# quad.net
KiCad netlist of a schematic drawn in EAGLE
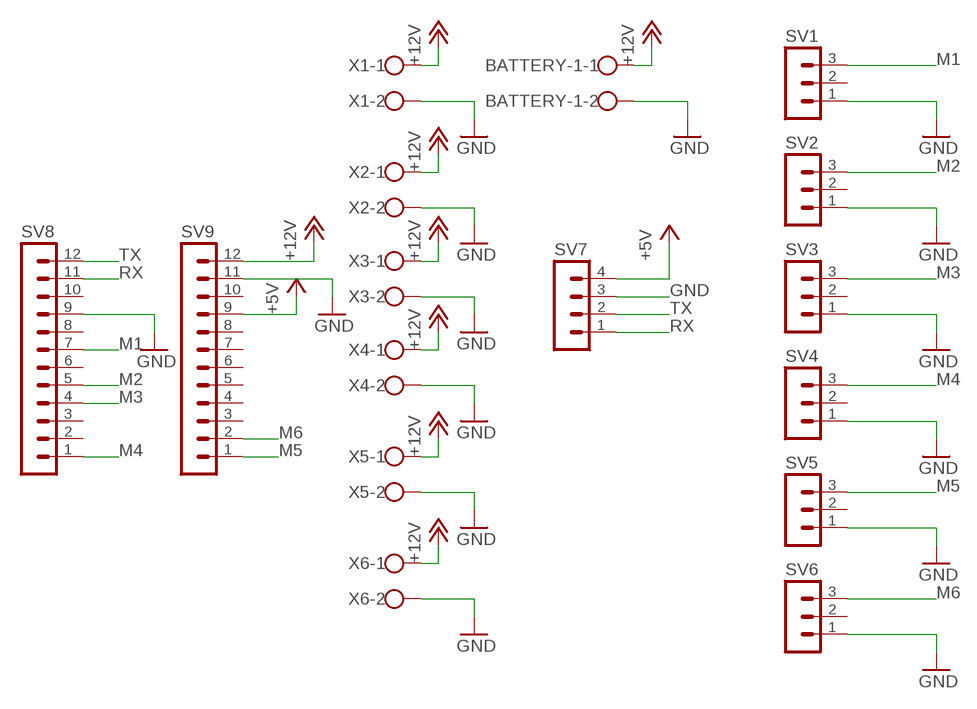
[diagram p0: schematic, sheet 1]

(export (version "E")
  (design (tool "Eeschema 10.0.6"))
  (components
    (comp (ref "BATTERY-1")
      (value "W237-102")
      (footprint "eagle-import:W237-102")
      (fields (field (name "MPN") "237-102"))
      (libsource (lib "eagle-import") (part "W237-102"))
    )
    (comp (ref "SV1")
      (value "MA03-1")
      (footprint "eagle-import:MA03-1")
      (libsource (lib "eagle-import") (part "MA03-1"))
    )
    (comp (ref "SV2")
      (value "MA03-1")
      (footprint "eagle-import:MA03-1")
      (libsource (lib "eagle-import") (part "MA03-1"))
    )
    (comp (ref "SV3")
      (value "MA03-1")
      (footprint "eagle-import:MA03-1")
      (libsource (lib "eagle-import") (part "MA03-1"))
    )
    (comp (ref "SV4")
      (value "MA03-1")
      (footprint "eagle-import:MA03-1")
      (libsource (lib "eagle-import") (part "MA03-1"))
    )
    (comp (ref "SV5")
      (value "MA03-1")
      (footprint "eagle-import:MA03-1")
      (libsource (lib "eagle-import") (part "MA03-1"))
    )
    (comp (ref "SV6")
      (value "MA03-1")
      (footprint "eagle-import:MA03-1")
      (libsource (lib "eagle-import") (part "MA03-1"))
    )
    (comp (ref "SV7")
      (value "MA04-1")
      (footprint "eagle-import:MA04-1")
      (libsource (lib "eagle-import") (part "MA04-1"))
    )
    (comp (ref "SV8")
      (value "MA12-1")
      (footprint "eagle-import:MA12-1")
      (libsource (lib "eagle-import") (part "MA12-1"))
    )
    (comp (ref "SV9")
      (value "MA12-1")
      (footprint "eagle-import:MA12-1")
      (libsource (lib "eagle-import") (part "MA12-1"))
    )
    (comp (ref "X1")
      (value "W237-102")
      (footprint "eagle-import:W237-102")
      (fields (field (name "MPN") "237-102"))
      (libsource (lib "eagle-import") (part "W237-102"))
    )
    (comp (ref "X2")
      (value "W237-102")
      (footprint "eagle-import:W237-102")
      (fields (field (name "MPN") "237-102"))
      (libsource (lib "eagle-import") (part "W237-102"))
    )
    (comp (ref "X3")
      (value "W237-102")
      (footprint "eagle-import:W237-102")
      (fields (field (name "MPN") "237-102"))
      (libsource (lib "eagle-import") (part "W237-102"))
    )
    (comp (ref "X4")
      (value "W237-102")
      (footprint "eagle-import:W237-102")
      (fields (field (name "MPN") "237-102"))
      (libsource (lib "eagle-import") (part "W237-102"))
    )
    (comp (ref "X5")
      (value "W237-102")
      (footprint "eagle-import:W237-102")
      (fields (field (name "MPN") "237-102"))
      (libsource (lib "eagle-import") (part "W237-102"))
    )
    (comp (ref "X6")
      (value "W237-102")
      (footprint "eagle-import:W237-102")
      (fields (field (name "MPN") "237-102"))
      (libsource (lib "eagle-import") (part "W237-102"))
    )
  )
  (nets
    (net (code "1") (name "+5V") (class "Default")
      (node (ref "SV7") (pin "4") (pinfunction "4_4") (pintype "passive"))
      (node (ref "SV9") (pin "9") (pinfunction "9_9") (pintype "passive"))
    )
    (net (code "2") (name "+12V") (class "Default")
      (node (ref "BATTERY-1") (pin "1") (pinfunction "KL_1") (pintype "passive"))
      (node (ref "SV9") (pin "12") (pinfunction "12_12") (pintype "passive"))
      (node (ref "X1") (pin "1") (pinfunction "KL_1") (pintype "passive"))
      (node (ref "X2") (pin "1") (pinfunction "KL_1") (pintype "passive"))
      (node (ref "X3") (pin "1") (pinfunction "KL_1") (pintype "passive"))
      (node (ref "X4") (pin "1") (pinfunction "KL_1") (pintype "passive"))
      (node (ref "X5") (pin "1") (pinfunction "KL_1") (pintype "passive"))
      (node (ref "X6") (pin "1") (pinfunction "KL_1") (pintype "passive"))
    )
    (net (code "3") (name "/M1") (class "Default")
      (node (ref "SV1") (pin "3") (pinfunction "3_3") (pintype "passive"))
      (node (ref "SV8") (pin "7") (pinfunction "7_7") (pintype "passive"))
    )
    (net (code "4") (name "/M2") (class "Default")
      (node (ref "SV2") (pin "3") (pinfunction "3_3") (pintype "passive"))
      (node (ref "SV8") (pin "5") (pinfunction "5_5") (pintype "passive"))
    )
    (net (code "5") (name "/M3") (class "Default")
      (node (ref "SV3") (pin "3") (pinfunction "3_3") (pintype "passive"))
      (node (ref "SV8") (pin "4") (pinfunction "4_4") (pintype "passive"))
    )
    (net (code "6") (name "/M4") (class "Default")
      (node (ref "SV4") (pin "3") (pinfunction "3_3") (pintype "passive"))
      (node (ref "SV8") (pin "1") (pinfunction "1_1") (pintype "passive"))
    )
    (net (code "7") (name "/M5") (class "Default")
      (node (ref "SV5") (pin "3") (pinfunction "3_3") (pintype "passive"))
      (node (ref "SV9") (pin "1") (pinfunction "1_1") (pintype "passive"))
    )
    (net (code "8") (name "/M6") (class "Default")
      (node (ref "SV6") (pin "3") (pinfunction "3_3") (pintype "passive"))
      (node (ref "SV9") (pin "2") (pinfunction "2_2") (pintype "passive"))
    )
    (net (code "9") (name "/RX") (class "Default")
      (node (ref "SV7") (pin "1") (pinfunction "1_1") (pintype "passive"))
      (node (ref "SV8") (pin "11") (pinfunction "11_11") (pintype "passive"))
    )
    (net (code "10") (name "/TX") (class "Default")
      (node (ref "SV7") (pin "2") (pinfunction "2_2") (pintype "passive"))
      (node (ref "SV8") (pin "12") (pinfunction "12_12") (pintype "passive"))
    )
    (net (code "11") (name "GND") (class "Default")
      (node (ref "BATTERY-1") (pin "2") (pinfunction "KL_2") (pintype "passive"))
      (node (ref "SV1") (pin "1") (pinfunction "1_1") (pintype "passive"))
      (node (ref "SV2") (pin "1") (pinfunction "1_1") (pintype "passive"))
      (node (ref "SV3") (pin "1") (pinfunction "1_1") (pintype "passive"))
      (node (ref "SV4") (pin "1") (pinfunction "1_1") (pintype "passive"))
      (node (ref "SV5") (pin "1") (pinfunction "1_1") (pintype "passive"))
      (node (ref "SV6") (pin "1") (pinfunction "1_1") (pintype "passive"))
      (node (ref "SV7") (pin "3") (pinfunction "3_3") (pintype "passive"))
      (node (ref "SV8") (pin "9") (pinfunction "9_9") (pintype "passive"))
      (node (ref "SV9") (pin "11") (pinfunction "11_11") (pintype "passive"))
      (node (ref "X1") (pin "2") (pinfunction "KL_2") (pintype "passive"))
      (node (ref "X2") (pin "2") (pinfunction "KL_2") (pintype "passive"))
      (node (ref "X3") (pin "2") (pinfunction "KL_2") (pintype "passive"))
      (node (ref "X4") (pin "2") (pinfunction "KL_2") (pintype "passive"))
      (node (ref "X5") (pin "2") (pinfunction "KL_2") (pintype "passive"))
      (node (ref "X6") (pin "2") (pinfunction "KL_2") (pintype "passive"))
    )
    (net (code "12") (name "unconnected-(SV1-Pad2)") (class "Default")
      (node (ref "SV1") (pin "2") (pinfunction "2_2") (pintype "passive"))
    )
    (net (code "13") (name "unconnected-(SV2-Pad2)") (class "Default")
      (node (ref "SV2") (pin "2") (pinfunction "2_2") (pintype "passive"))
    )
    (net (code "14") (name "unconnected-(SV3-Pad2)") (class "Default")
      (node (ref "SV3") (pin "2") (pinfunction "2_2") (pintype "passive"))
    )
    (net (code "15") (name "unconnected-(SV4-Pad2)") (class "Default")
      (node (ref "SV4") (pin "2") (pinfunction "2_2") (pintype "passive"))
    )
    (net (code "16") (name "unconnected-(SV5-Pad2)") (class "Default")
      (node (ref "SV5") (pin "2") (pinfunction "2_2") (pintype "passive"))
    )
    (net (code "17") (name "unconnected-(SV6-Pad2)") (class "Default")
      (node (ref "SV6") (pin "2") (pinfunction "2_2") (pintype "passive"))
    )
    (net (code "18") (name "unconnected-(SV8-Pad2)") (class "Default")
      (node (ref "SV8") (pin "2") (pinfunction "2_2") (pintype "passive"))
    )
    (net (code "19") (name "unconnected-(SV8-Pad3)") (class "Default")
      (node (ref "SV8") (pin "3") (pinfunction "3_3") (pintype "passive"))
    )
    (net (code "20") (name "unconnected-(SV8-Pad6)") (class "Default")
      (node (ref "SV8") (pin "6") (pinfunction "6_6") (pintype "passive"))
    )
    (net (code "21") (name "unconnected-(SV8-Pad8)") (class "Default")
      (node (ref "SV8") (pin "8") (pinfunction "8_8") (pintype "passive"))
    )
    (net (code "22") (name "unconnected-(SV8-Pad10)") (class "Default")
      (node (ref "SV8") (pin "10") (pinfunction "10_10") (pintype "passive"))
    )
    (net (code "23") (name "unconnected-(SV9-Pad3)") (class "Default")
      (node (ref "SV9") (pin "3") (pinfunction "3_3") (pintype "passive"))
    )
    (net (code "24") (name "unconnected-(SV9-Pad4)") (class "Default")
      (node (ref "SV9") (pin "4") (pinfunction "4_4") (pintype "passive"))
    )
    (net (code "25") (name "unconnected-(SV9-Pad5)") (class "Default")
      (node (ref "SV9") (pin "5") (pinfunction "5_5") (pintype "passive"))
    )
    (net (code "26") (name "unconnected-(SV9-Pad6)") (class "Default")
      (node (ref "SV9") (pin "6") (pinfunction "6_6") (pintype "passive"))
    )
    (net (code "27") (name "unconnected-(SV9-Pad7)") (class "Default")
      (node (ref "SV9") (pin "7") (pinfunction "7_7") (pintype "passive"))
    )
    (net (code "28") (name "unconnected-(SV9-Pad8)") (class "Default")
      (node (ref "SV9") (pin "8") (pinfunction "8_8") (pintype "passive"))
    )
    (net (code "29") (name "unconnected-(SV9-Pad10)") (class "Default")
      (node (ref "SV9") (pin "10") (pinfunction "10_10") (pintype "passive"))
    )
  )
)
